# untitled.net
KiCad netlist of a schematic drawn in EAGLE
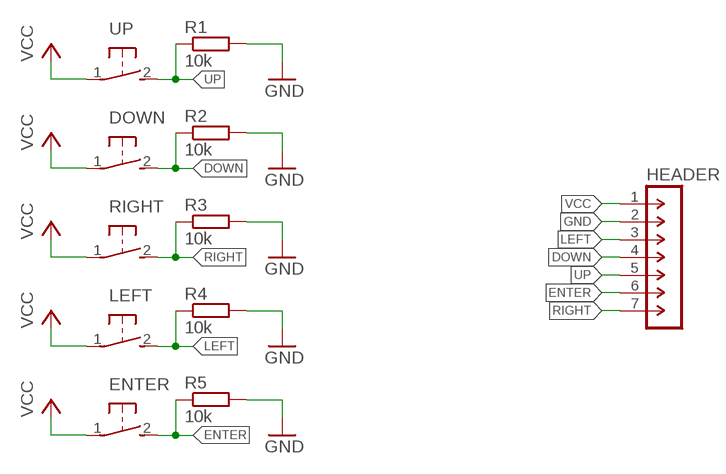
[diagram p0: schematic, sheet 1]

(export (version "E")
  (design (tool "Eeschema 10.0.6"))
  (components
    (comp (ref "DOWN")
      (value "DTSM-3")
      (footprint "eagle-import:DTSM-3")
      (libsource (lib "eagle-import") (part "DTSM-3"))
    )
    (comp (ref "ENTER")
      (value "DTSM-3")
      (footprint "eagle-import:DTSM-3")
      (libsource (lib "eagle-import") (part "DTSM-3"))
    )
    (comp (ref "HEADER")
      (value "M-1X07-SIP-100-32Y")
      (footprint "eagle-import:SIP-100-07-32Y")
      (libsource (lib "eagle-import") (part "M-1X07-SIP-100-32Y"))
    )
    (comp (ref "LEFT")
      (value "DTSM-3")
      (footprint "eagle-import:DTSM-3")
      (libsource (lib "eagle-import") (part "DTSM-3"))
    )
    (comp (ref "R1")
      (value "10k")
      (footprint "eagle-import:R1206")
      (libsource (lib "eagle-import") (part "R-EU_R1206"))
    )
    (comp (ref "R2")
      (value "10k")
      (footprint "eagle-import:R1206")
      (libsource (lib "eagle-import") (part "R-EU_R1206"))
    )
    (comp (ref "R3")
      (value "10k")
      (footprint "eagle-import:R1206")
      (libsource (lib "eagle-import") (part "R-EU_R1206"))
    )
    (comp (ref "R4")
      (value "10k")
      (footprint "eagle-import:R1206")
      (libsource (lib "eagle-import") (part "R-EU_R1206"))
    )
    (comp (ref "R5")
      (value "10k")
      (footprint "eagle-import:R1206")
      (libsource (lib "eagle-import") (part "R-EU_R1206"))
    )
    (comp (ref "RIGHT")
      (value "DTSM-3")
      (footprint "eagle-import:DTSM-3")
      (libsource (lib "eagle-import") (part "DTSM-3"))
    )
    (comp (ref "UP")
      (value "DTSM-3")
      (footprint "eagle-import:DTSM-3")
      (libsource (lib "eagle-import") (part "DTSM-3"))
    )
  )
  (nets
    (net (code "1") (name "DOWN") (class "Default")
      (node (ref "DOWN") (pin "2") (pinfunction "2_2") (pintype "passive"))
      (node (ref "HEADER") (pin "4") (pinfunction "4_4") (pintype "passive"))
      (node (ref "R2") (pin "1") (pinfunction "1_1") (pintype "passive"))
    )
    (net (code "2") (name "ENTER") (class "Default")
      (node (ref "ENTER") (pin "2") (pinfunction "2_2") (pintype "passive"))
      (node (ref "HEADER") (pin "6") (pinfunction "6_6") (pintype "passive"))
      (node (ref "R5") (pin "1") (pinfunction "1_1") (pintype "passive"))
    )
    (net (code "3") (name "GND") (class "Default")
      (node (ref "HEADER") (pin "2") (pinfunction "2_2") (pintype "passive"))
      (node (ref "R1") (pin "2") (pinfunction "2_2") (pintype "passive"))
      (node (ref "R2") (pin "2") (pinfunction "2_2") (pintype "passive"))
      (node (ref "R3") (pin "2") (pinfunction "2_2") (pintype "passive"))
      (node (ref "R4") (pin "2") (pinfunction "2_2") (pintype "passive"))
      (node (ref "R5") (pin "2") (pinfunction "2_2") (pintype "passive"))
    )
    (net (code "4") (name "LEFT") (class "Default")
      (node (ref "HEADER") (pin "3") (pinfunction "3_3") (pintype "passive"))
      (node (ref "LEFT") (pin "2") (pinfunction "2_2") (pintype "passive"))
      (node (ref "R4") (pin "1") (pinfunction "1_1") (pintype "passive"))
    )
    (net (code "5") (name "RIGHT") (class "Default")
      (node (ref "HEADER") (pin "7") (pinfunction "7_7") (pintype "passive"))
      (node (ref "R3") (pin "1") (pinfunction "1_1") (pintype "passive"))
      (node (ref "RIGHT") (pin "2") (pinfunction "2_2") (pintype "passive"))
    )
    (net (code "6") (name "UP") (class "Default")
      (node (ref "HEADER") (pin "5") (pinfunction "5_5") (pintype "passive"))
      (node (ref "R1") (pin "1") (pinfunction "1_1") (pintype "passive"))
      (node (ref "UP") (pin "2") (pinfunction "2_2") (pintype "passive"))
    )
    (net (code "7") (name "VCC") (class "Default")
      (node (ref "DOWN") (pin "1") (pinfunction "1_1") (pintype "passive"))
      (node (ref "ENTER") (pin "1") (pinfunction "1_1") (pintype "passive"))
      (node (ref "HEADER") (pin "1") (pinfunction "1_1") (pintype "passive"))
      (node (ref "LEFT") (pin "1") (pinfunction "1_1") (pintype "passive"))
      (node (ref "RIGHT") (pin "1") (pinfunction "1_1") (pintype "passive"))
      (node (ref "UP") (pin "1") (pinfunction "1_1") (pintype "passive"))
    )
  )
)
